# Printrhub_Rev_1.net
KiCad netlist of a schematic drawn in EAGLE
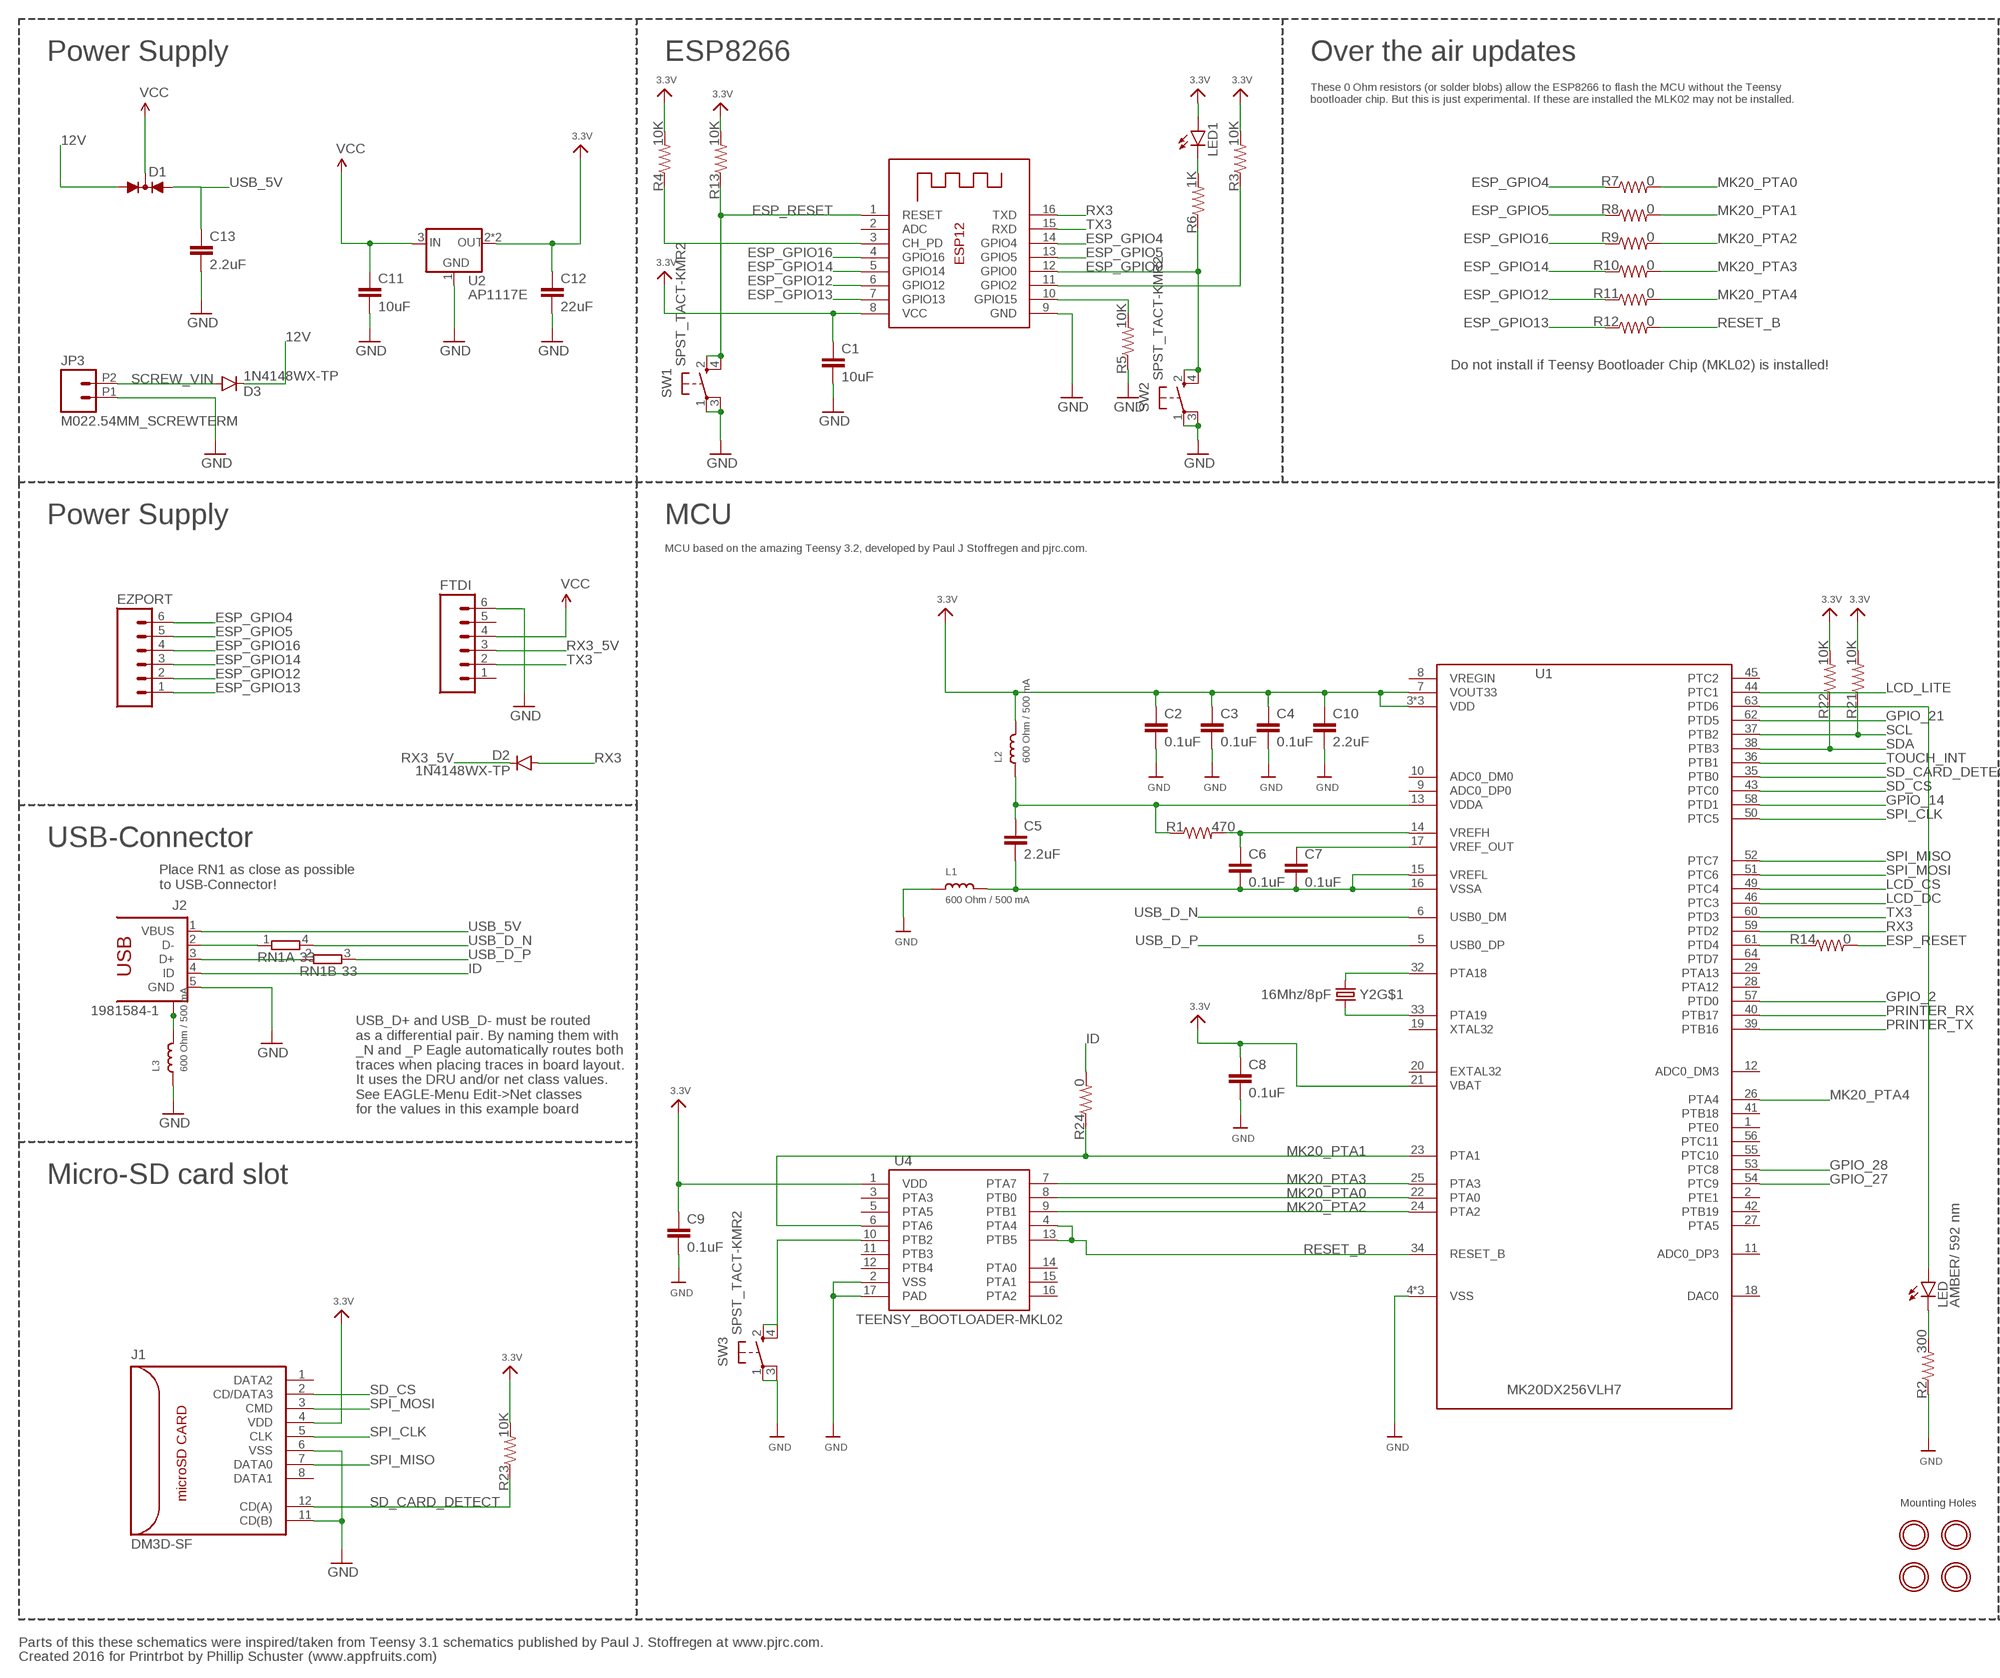
[diagram p0: schematic, sheet 1, part 1 of 2]
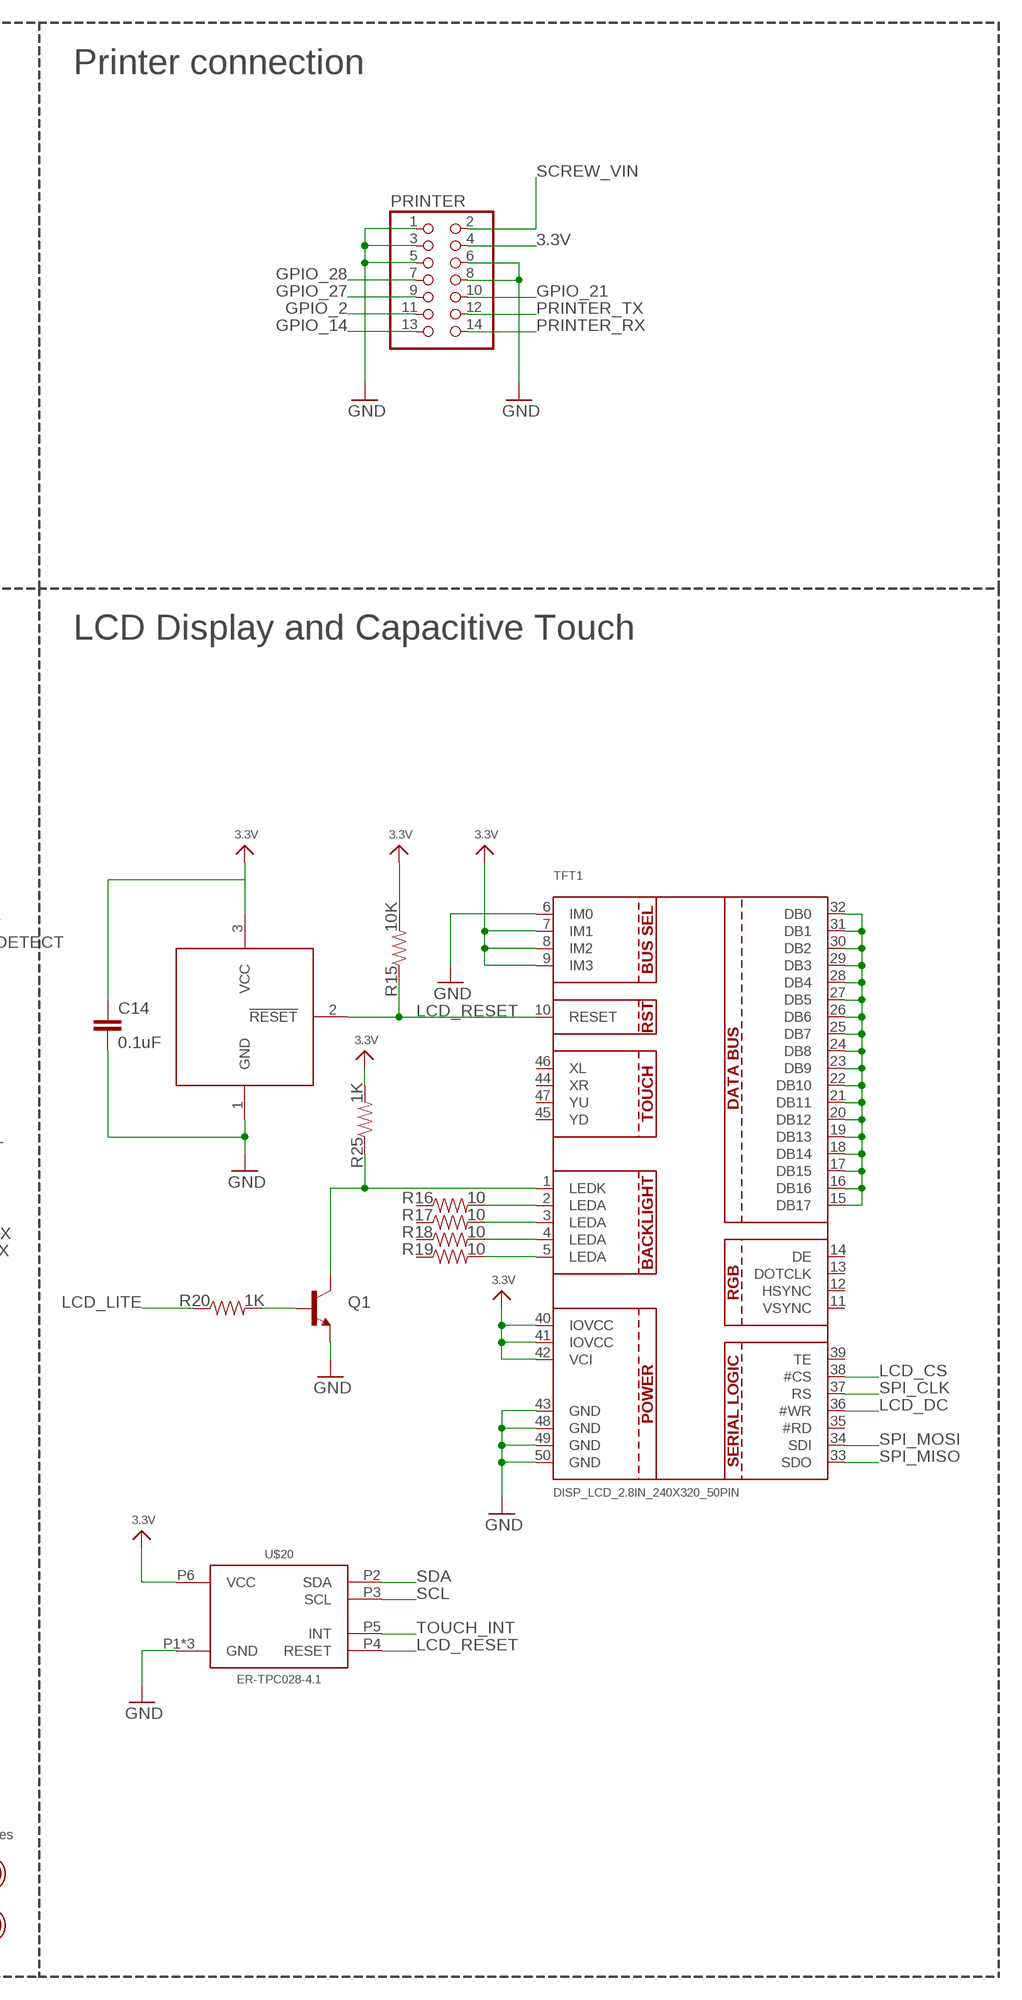
[diagram p1: schematic, sheet 1, part 2 of 2]

(export (version "E")
  (design (tool "Eeschema 10.0.6"))
  (components
    (comp (ref "C1")
      (value "10uF")
      (footprint "eagle-import:0603-CAP")
      (fields (field (name "MF") "Murata") (field (name "MPN") "GRM188R60J106ME47D"))
      (libsource (lib "eagle-import") (part "CAPACITOR-10UF"))
    )
    (comp (ref "C2")
      (value "0.1uF")
      (footprint "eagle-import:0603-CAP")
      (fields (field (name "MF") "Kemet") (field (name "MPN") "C0603C104J3RACTU"))
      (libsource (lib "eagle-import") (part "CAPACITOR-0.1UF"))
    )
    (comp (ref "C3")
      (value "0.1uF")
      (footprint "eagle-import:0603-CAP")
      (fields (field (name "MF") "Kemet") (field (name "MPN") "C0603C104J3RACTU"))
      (libsource (lib "eagle-import") (part "CAPACITOR-0.1UF"))
    )
    (comp (ref "C4")
      (value "0.1uF")
      (footprint "eagle-import:0603-CAP")
      (fields (field (name "MF") "Kemet") (field (name "MPN") "C0603C104J3RACTU"))
      (libsource (lib "eagle-import") (part "CAPACITOR-0.1UF"))
    )
    (comp (ref "C5")
      (value "2.2uF")
      (footprint "eagle-import:0603-CAP")
      (fields (field (name "MF") "Kemet") (field (name "MPN") "C0603C225K4PACTU"))
      (libsource (lib "eagle-import") (part "CAPACITOR-2.2UF"))
    )
    (comp (ref "C6")
      (value "0.1uF")
      (footprint "eagle-import:0603-CAP")
      (fields (field (name "MF") "Kemet") (field (name "MPN") "C0603C104J3RACTU"))
      (libsource (lib "eagle-import") (part "CAPACITOR-0.1UF"))
    )
    (comp (ref "C7")
      (value "0.1uF")
      (footprint "eagle-import:0603-CAP")
      (fields (field (name "MF") "Kemet") (field (name "MPN") "C0603C104J3RACTU"))
      (libsource (lib "eagle-import") (part "CAPACITOR-0.1UF"))
    )
    (comp (ref "C8")
      (value "0.1uF")
      (footprint "eagle-import:0603-CAP")
      (fields (field (name "MF") "Kemet") (field (name "MPN") "C0603C104J3RACTU"))
      (libsource (lib "eagle-import") (part "CAPACITOR-0.1UF"))
    )
    (comp (ref "C9")
      (value "0.1uF")
      (footprint "eagle-import:0603-CAP")
      (fields (field (name "MF") "Kemet") (field (name "MPN") "C0603C104J3RACTU"))
      (libsource (lib "eagle-import") (part "CAPACITOR-0.1UF"))
    )
    (comp (ref "C10")
      (value "2.2uF")
      (footprint "eagle-import:0603-CAP")
      (fields (field (name "MF") "Kemet") (field (name "MPN") "C0603C225K4PACTU"))
      (libsource (lib "eagle-import") (part "CAPACITOR-2.2UF"))
    )
    (comp (ref "C11")
      (value "10uF")
      (footprint "eagle-import:0603-CAP")
      (fields (field (name "MF") "Murata") (field (name "MPN") "GRM188R60J106ME47D"))
      (libsource (lib "eagle-import") (part "CAPACITOR-10UF"))
    )
    (comp (ref "C12")
      (value "22uF")
      (footprint "eagle-import:0603-CAP")
      (fields (field (name "MF") "Murata") (field (name "MPN") "GRM188R60J226MEA0D"))
      (libsource (lib "eagle-import") (part "CAPACITOR-22UF"))
    )
    (comp (ref "C13")
      (value "2.2uF")
      (footprint "eagle-import:0603-CAP")
      (fields (field (name "MF") "Kemet") (field (name "MPN") "C0603C225K4PACTU"))
      (libsource (lib "eagle-import") (part "CAPACITOR-2.2UF"))
    )
    (comp (ref "C14")
      (value "0.1uF")
      (footprint "eagle-import:0603-CAP")
      (fields (field (name "MF") "Kemet") (field (name "MPN") "C0603C104J3RACTU"))
      (libsource (lib "eagle-import") (part "CAPACITOR-0.1UF"))
    )
    (comp (ref "D1")
      (value "DIODE-2AC|CASOT23")
      (footprint "eagle-import:SOT23")
      (libsource (lib "eagle-import") (part "DIODE-2AC|CASOT23"))
    )
    (comp (ref "D2")
      (value "1N4148WX-TP")
      (footprint "eagle-import:SOD-323")
      (fields (field (name "MF") "Micro Commercial Co"))
      (libsource (lib "eagle-import") (part "DIODESOD"))
    )
    (comp (ref "D3")
      (value "1N4148WX-TP")
      (footprint "eagle-import:SOD-323")
      (fields (field (name "MF") "Micro Commercial Co"))
      (libsource (lib "eagle-import") (part "DIODESOD"))
    )
    (comp (ref "EZPORT")
      (value "M06SMD-STRAIGHT")
      (footprint "eagle-import:1X06_SMD_STRAIGHT")
      (libsource (lib "eagle-import") (part "M06SMD-STRAIGHT"))
    )
    (comp (ref "FTDI")
      (value "M06SMD-STRAIGHT")
      (footprint "eagle-import:1X06_SMD_STRAIGHT")
      (libsource (lib "eagle-import") (part "M06SMD-STRAIGHT"))
    )
    (comp (ref "J1")
      (value "DM3D-SF")
      (footprint "eagle-import:DM3D-SF")
      (libsource (lib "eagle-import") (part "DM3D-SF"))
    )
    (comp (ref "J2")
      (value "1981584-1")
      (footprint "eagle-import:1981584-1")
      (libsource (lib "eagle-import") (part "1981584-1"))
    )
    (comp (ref "JP3")
      (value "M022.54MM_SCREWTERM")
      (footprint "eagle-import:1X02_2.54_SCREWTERM")
      (libsource (lib "eagle-import") (part "M022.54MM_SCREWTERM"))
    )
    (comp (ref "L1")
      (value "600 Ohm / 500 mA")
      (footprint "eagle-import:0603")
      (fields (field (name "MF") "Murata") (field (name "MPN") "BLM18AG601SN1D"))
      (libsource (lib "eagle-import") (part "INDUCTOR-0603_600OHM/500MA"))
    )
    (comp (ref "L2")
      (value "600 Ohm / 500 mA")
      (footprint "eagle-import:0603")
      (fields (field (name "MF") "Murata") (field (name "MPN") "BLM18AG601SN1D"))
      (libsource (lib "eagle-import") (part "INDUCTOR-0603_600OHM/500MA"))
    )
    (comp (ref "L3")
      (value "600 Ohm / 500 mA")
      (footprint "eagle-import:0603")
      (fields (field (name "MF") "Murata") (field (name "MPN") "BLM18AG601SN1D"))
      (libsource (lib "eagle-import") (part "INDUCTOR-0603_600OHM/500MA"))
    )
    (comp (ref "LED")
      (value "AMBER/ 592 nm")
      (footprint "eagle-import:LED-0603")
      (fields (field (name "MF") "Avago Technologies") (field (name "MPN") "HSMA-C190"))
      (libsource (lib "eagle-import") (part "LED-AMBER"))
    )
    (comp (ref "LED1")
      (value "LED-GREEN")
      (footprint "eagle-import:LED-0603")
      (fields (field (name "MF") "Avago") (field (name "MPN") "HSMG-C190"))
      (libsource (lib "eagle-import") (part "LED-GREEN"))
    )
    (comp (ref "PRINTER")
      (value "PINHD-2X7SMT")
      (footprint "eagle-import:2X07_SMT")
      (libsource (lib "eagle-import") (part "PINHD-2X7SMT"))
    )
    (comp (ref "Q1")
      (value "TRANSISTOR_NPNSOT23-3")
      (footprint "eagle-import:SOT23-3")
      (fields (field (name "MF") "ON Semiconductor") (field (name "MPN") "MMBT2222ALT1G"))
      (libsource (lib "eagle-import") (part "TRANSISTOR_NPNSOT23-3"))
    )
    (comp (ref "R1")
      (value "470")
      (footprint "eagle-import:0603-RES")
      (fields (field (name "MF") "Panasonic") (field (name "MPN") "ERJ-3GEYJ471V"))
      (libsource (lib "eagle-import") (part "RESISTOR-470"))
    )
    (comp (ref "R2")
      (value "300")
      (footprint "eagle-import:0603-RES")
      (libsource (lib "eagle-import") (part "RESISTOR0603"))
    )
    (comp (ref "R3")
      (value "10K")
      (footprint "eagle-import:0603-RES")
      (fields (field (name "MF") "Panasonic") (field (name "MPN") "ERJ-3GEYJ103V"))
      (libsource (lib "eagle-import") (part "RESISTOR-10K"))
    )
    (comp (ref "R4")
      (value "10K")
      (footprint "eagle-import:0603-RES")
      (fields (field (name "MF") "Panasonic") (field (name "MPN") "ERJ-3GEYJ103V"))
      (libsource (lib "eagle-import") (part "RESISTOR-10K"))
    )
    (comp (ref "R5")
      (value "10K")
      (footprint "eagle-import:0603-RES")
      (fields (field (name "MF") "Panasonic") (field (name "MPN") "ERJ-3GEYJ103V"))
      (libsource (lib "eagle-import") (part "RESISTOR-10K"))
    )
    (comp (ref "R6")
      (value "1K")
      (footprint "eagle-import:0603-RES")
      (fields (field (name "MF") "Panasonic") (field (name "MPN") "ERJ-3GEYJ102V"))
      (libsource (lib "eagle-import") (part "RESISTOR-1K"))
    )
    (comp (ref "R7")
      (value "0")
      (footprint "eagle-import:0603-RES")
      (fields (field (name "MF") "Panasonic") (field (name "MPN") "ERJ-3GEY0R00V"))
      (libsource (lib "eagle-import") (part "RESISTOR-0"))
    )
    (comp (ref "R8")
      (value "0")
      (footprint "eagle-import:0603-RES")
      (fields (field (name "MF") "Panasonic") (field (name "MPN") "ERJ-3GEY0R00V"))
      (libsource (lib "eagle-import") (part "RESISTOR-0"))
    )
    (comp (ref "R9")
      (value "0")
      (footprint "eagle-import:0603-RES")
      (fields (field (name "MF") "Panasonic") (field (name "MPN") "ERJ-3GEY0R00V"))
      (libsource (lib "eagle-import") (part "RESISTOR-0"))
    )
    (comp (ref "R10")
      (value "0")
      (footprint "eagle-import:0603-RES")
      (fields (field (name "MF") "Panasonic") (field (name "MPN") "ERJ-3GEY0R00V"))
      (libsource (lib "eagle-import") (part "RESISTOR-0"))
    )
    (comp (ref "R11")
      (value "0")
      (footprint "eagle-import:0603-RES")
      (fields (field (name "MF") "Panasonic") (field (name "MPN") "ERJ-3GEY0R00V"))
      (libsource (lib "eagle-import") (part "RESISTOR-0"))
    )
    (comp (ref "R12")
      (value "0")
      (footprint "eagle-import:0603-RES")
      (fields (field (name "MF") "Panasonic") (field (name "MPN") "ERJ-3GEY0R00V"))
      (libsource (lib "eagle-import") (part "RESISTOR-0"))
    )
    (comp (ref "R13")
      (value "10K")
      (footprint "eagle-import:0603-RES")
      (fields (field (name "MF") "Panasonic") (field (name "MPN") "ERJ-3GEYJ103V"))
      (libsource (lib "eagle-import") (part "RESISTOR-10K"))
    )
    (comp (ref "R14")
      (value "0")
      (footprint "eagle-import:0603-RES")
      (fields (field (name "MF") "Panasonic") (field (name "MPN") "ERJ-3GEY0R00V"))
      (libsource (lib "eagle-import") (part "RESISTOR-0"))
    )
    (comp (ref "R15")
      (value "10K")
      (footprint "eagle-import:0603-RES")
      (fields (field (name "MF") "Panasonic") (field (name "MPN") "ERJ-3GEYJ103V"))
      (libsource (lib "eagle-import") (part "RESISTOR-10K"))
    )
    (comp (ref "R16")
      (value "10")
      (footprint "eagle-import:0603-RES")
      (fields (field (name "MF") "Panasonic") (field (name "MPN") "ERJ-3EKF10R0V"))
      (libsource (lib "eagle-import") (part "RESISTOR-10"))
    )
    (comp (ref "R17")
      (value "10")
      (footprint "eagle-import:0603-RES")
      (fields (field (name "MF") "Panasonic") (field (name "MPN") "ERJ-3EKF10R0V"))
      (libsource (lib "eagle-import") (part "RESISTOR-10"))
    )
    (comp (ref "R18")
      (value "10")
      (footprint "eagle-import:0603-RES")
      (fields (field (name "MF") "Panasonic") (field (name "MPN") "ERJ-3EKF10R0V"))
      (libsource (lib "eagle-import") (part "RESISTOR-10"))
    )
    (comp (ref "R19")
      (value "10")
      (footprint "eagle-import:0603-RES")
      (fields (field (name "MF") "Panasonic") (field (name "MPN") "ERJ-3EKF10R0V"))
      (libsource (lib "eagle-import") (part "RESISTOR-10"))
    )
    (comp (ref "R20")
      (value "1K")
      (footprint "eagle-import:0603-RES")
      (fields (field (name "MF") "Panasonic") (field (name "MPN") "ERJ-3GEYJ102V"))
      (libsource (lib "eagle-import") (part "RESISTOR-1K"))
    )
    (comp (ref "R21")
      (value "10K")
      (footprint "eagle-import:0603-RES")
      (fields (field (name "MF") "Panasonic") (field (name "MPN") "ERJ-3GEYJ103V"))
      (libsource (lib "eagle-import") (part "RESISTOR-10K"))
    )
    (comp (ref "R22")
      (value "10K")
      (footprint "eagle-import:0603-RES")
      (fields (field (name "MF") "Panasonic") (field (name "MPN") "ERJ-3GEYJ103V"))
      (libsource (lib "eagle-import") (part "RESISTOR-10K"))
    )
    (comp (ref "R23")
      (value "10K")
      (footprint "eagle-import:0603-RES")
      (fields (field (name "MF") "Panasonic") (field (name "MPN") "ERJ-3GEYJ103V"))
      (libsource (lib "eagle-import") (part "RESISTOR-10K"))
    )
    (comp (ref "R24")
      (value "0")
      (footprint "eagle-import:0603-RES")
      (fields (field (name "MF") "Panasonic") (field (name "MPN") "ERJ-3GEY0R00V"))
      (libsource (lib "eagle-import") (part "RESISTOR-0"))
    )
    (comp (ref "R25")
      (value "1K")
      (footprint "eagle-import:0603-RES")
      (fields (field (name "MF") "Panasonic") (field (name "MPN") "ERJ-3GEYJ102V"))
      (libsource (lib "eagle-import") (part "RESISTOR-1K"))
    )
    (comp (ref "RN1")
      (value "33")
      (footprint "eagle-import:EXB34V")
      (fields (field (name "MF") "Panasonic") (field (name "MPN") "EXB-34V330JV"))
      (libsource (lib "eagle-import") (part "2R-NEXB34V"))
    )
    (comp (ref "SW1")
      (value "SPST_TACT-KMR2")
      (footprint "eagle-import:KMR2")
      (libsource (lib "eagle-import") (part "SPST_TACT-KMR2"))
    )
    (comp (ref "SW2")
      (value "SPST_TACT-KMR2")
      (footprint "eagle-import:KMR2")
      (libsource (lib "eagle-import") (part "SPST_TACT-KMR2"))
    )
    (comp (ref "SW3")
      (value "SPST_TACT-KMR2")
      (footprint "eagle-import:KMR2")
      (libsource (lib "eagle-import") (part "SPST_TACT-KMR2"))
    )
    (comp (ref "TFT1")
      (value "DISP_LCD_2.8IN_240X320_50PIN")
      (footprint "eagle-import:TFT_2.83IN_240X320_50PIN")
      (libsource (lib "eagle-import") (part "DISP_LCD_2.8IN_240X320_50PIN"))
    )
    (comp (ref "U$15")
      (value "MOUNTINGHOLE2.0")
      (footprint "eagle-import:MOUNTINGHOLE_2.0_PLATED")
      (libsource (lib "eagle-import") (part "MOUNTINGHOLE2.0"))
    )
    (comp (ref "U$16")
      (value "MOUNTINGHOLE2.0")
      (footprint "eagle-import:MOUNTINGHOLE_2.0_PLATED")
      (libsource (lib "eagle-import") (part "MOUNTINGHOLE2.0"))
    )
    (comp (ref "U$17")
      (value "MOUNTINGHOLE2.0")
      (footprint "eagle-import:MOUNTINGHOLE_2.0_PLATED")
      (libsource (lib "eagle-import") (part "MOUNTINGHOLE2.0"))
    )
    (comp (ref "U$18")
      (value "MOUNTINGHOLE2.0")
      (footprint "eagle-import:MOUNTINGHOLE_2.0_PLATED")
      (libsource (lib "eagle-import") (part "MOUNTINGHOLE2.0"))
    )
    (comp (ref "U$20")
      (value "ER-TPC028-4.1")
      (footprint "eagle-import:ER-CON06HB-1")
      (libsource (lib "eagle-import") (part "ER-TPC028-4.1"))
    )
    (comp (ref "U1")
      (value "MK20DX256VLH7")
      (footprint "eagle-import:MK20DX256VLH7")
      (fields (field (name "MF") "Freescale"))
      (libsource (lib "eagle-import") (part "MK20DX256VLH7"))
    )
    (comp (ref "U2")
      (value "AP1117E")
      (footprint "eagle-import:SOT223")
      (libsource (lib "eagle-import") (part "AP1117E"))
    )
    (comp (ref "U3")
      (value "MAX308-SOT23")
      (footprint "eagle-import:SOT23")
      (libsource (lib "eagle-import") (part "MAX308-SOT23"))
    )
    (comp (ref "U4")
      (value "TEENSY_BOOTLOADER-MKL02")
      (footprint "eagle-import:QFN50P300X300X100-17N")
      (libsource (lib "eagle-import") (part "TEENSY_BOOTLOADER-MKL02"))
    )
    (comp (ref "X1")
      (value "ESP-12")
      (footprint "eagle-import:ESP-12")
      (libsource (lib "eagle-import") (part "ESP-12"))
    )
    (comp (ref "Y2")
      (value "16Mhz/8pF")
      (footprint "eagle-import:CRYSTAL-SMD-5X3")
      (fields (field (name "MF") "ECS") (field (name "MPN") "ECS-160-8-30B-CKM"))
      (libsource (lib "eagle-import") (part "CRYSTAL/SMD-5X3-GND16MHZ/8PF"))
    )
  )
  (nets
    (net (code "1") (name "/12V") (class "Default")
      (node (ref "D1") (pin "1") (pinfunction "A1_1") (pintype "passive"))
      (node (ref "D3") (pin "C") (pinfunction "C_C") (pintype "passive"))
    )
    (net (code "2") (name "/ESP_GPIO0") (class "Default")
      (node (ref "R6") (pin "1") (pinfunction "1_1") (pintype "passive"))
      (node (ref "SW2") (pin "2") (pinfunction "S_2") (pintype "passive"))
      (node (ref "SW2") (pin "4") (pinfunction "S1_4") (pintype "passive"))
      (node (ref "X1") (pin "12") (pinfunction "GPIO0_12") (pintype "bidirectional"))
    )
    (net (code "3") (name "/ESP_GPIO4") (class "Default")
      (node (ref "EZPORT") (pin "6") (pinfunction "6_6") (pintype "passive"))
      (node (ref "R7") (pin "1") (pinfunction "1_1") (pintype "passive"))
      (node (ref "X1") (pin "14") (pinfunction "GPIO4_14") (pintype "bidirectional"))
    )
    (net (code "4") (name "/ESP_GPIO5") (class "Default")
      (node (ref "EZPORT") (pin "5") (pinfunction "5_5") (pintype "passive"))
      (node (ref "R8") (pin "1") (pinfunction "1_1") (pintype "passive"))
      (node (ref "X1") (pin "13") (pinfunction "GPIO5_13") (pintype "bidirectional"))
    )
    (net (code "5") (name "/ESP_GPIO12") (class "Default")
      (node (ref "EZPORT") (pin "2") (pinfunction "2_2") (pintype "passive"))
      (node (ref "R11") (pin "1") (pinfunction "1_1") (pintype "passive"))
      (node (ref "X1") (pin "6") (pinfunction "GPIO12_6") (pintype "bidirectional"))
    )
    (net (code "6") (name "/ESP_GPIO13") (class "Default")
      (node (ref "EZPORT") (pin "1") (pinfunction "1_1") (pintype "passive"))
      (node (ref "R12") (pin "1") (pinfunction "1_1") (pintype "passive"))
      (node (ref "X1") (pin "7") (pinfunction "GPIO13_7") (pintype "bidirectional"))
    )
    (net (code "7") (name "/ESP_GPIO14") (class "Default")
      (node (ref "EZPORT") (pin "3") (pinfunction "3_3") (pintype "passive"))
      (node (ref "R10") (pin "1") (pinfunction "1_1") (pintype "passive"))
      (node (ref "X1") (pin "5") (pinfunction "GPIO14_5") (pintype "bidirectional"))
    )
    (net (code "8") (name "/ESP_GPIO16") (class "Default")
      (node (ref "EZPORT") (pin "4") (pinfunction "4_4") (pintype "passive"))
      (node (ref "R9") (pin "1") (pinfunction "1_1") (pintype "passive"))
      (node (ref "X1") (pin "4") (pinfunction "GPIO16_4") (pintype "bidirectional"))
    )
    (net (code "9") (name "/ESP_RESET") (class "Default")
      (node (ref "R13") (pin "1") (pinfunction "1_1") (pintype "passive"))
      (node (ref "R14") (pin "2") (pinfunction "2_2") (pintype "passive"))
      (node (ref "SW1") (pin "2") (pinfunction "S_2") (pintype "passive"))
      (node (ref "SW1") (pin "4") (pinfunction "S1_4") (pintype "passive"))
      (node (ref "X1") (pin "1") (pinfunction "RESET_1") (pintype "input"))
    )
    (net (code "10") (name "/GPIO_2") (class "Default")
      (node (ref "PRINTER") (pin "11") (pinfunction "11_11") (pintype "passive"))
      (node (ref "U1") (pin "57") (pinfunction "PTD0_57") (pintype "bidirectional"))
    )
    (net (code "11") (name "/GPIO_14") (class "Default")
      (node (ref "PRINTER") (pin "13") (pinfunction "13_13") (pintype "passive"))
      (node (ref "U1") (pin "58") (pinfunction "PTD1_58") (pintype "bidirectional"))
    )
    (net (code "12") (name "/GPIO_21") (class "Default")
      (node (ref "PRINTER") (pin "10") (pinfunction "10_10") (pintype "passive"))
      (node (ref "U1") (pin "62") (pinfunction "PTD5_62") (pintype "bidirectional"))
    )
    (net (code "13") (name "/GPIO_27") (class "Default")
      (node (ref "PRINTER") (pin "9") (pinfunction "9_9") (pintype "passive"))
      (node (ref "U1") (pin "54") (pinfunction "PTC9_54") (pintype "bidirectional"))
    )
    (net (code "14") (name "/GPIO_28") (class "Default")
      (node (ref "PRINTER") (pin "7") (pinfunction "7_7") (pintype "passive"))
      (node (ref "U1") (pin "53") (pinfunction "PTC8_53") (pintype "bidirectional"))
    )
    (net (code "15") (name "/ID") (class "Default")
      (node (ref "J2") (pin "4") (pinfunction "ID_4") (pintype "passive"))
      (node (ref "R24") (pin "2") (pinfunction "2_2") (pintype "passive"))
    )
    (net (code "16") (name "/LCD_CS") (class "Default")
      (node (ref "TFT1") (pin "38") (pinfunction "#CS_38") (pintype "bidirectional"))
      (node (ref "U1") (pin "49") (pinfunction "PTC4_49") (pintype "bidirectional"))
    )
    (net (code "17") (name "/LCD_DC") (class "Default")
      (node (ref "TFT1") (pin "36") (pinfunction "#WR_36") (pintype "bidirectional"))
      (node (ref "U1") (pin "46") (pinfunction "PTC3_46") (pintype "bidirectional"))
    )
    (net (code "18") (name "/LCD_LITE") (class "Default")
      (node (ref "R20") (pin "1") (pinfunction "1_1") (pintype "passive"))
      (node (ref "U1") (pin "44") (pinfunction "PTC1_44") (pintype "bidirectional"))
    )
    (net (code "19") (name "/LCD_RESET") (class "Default")
      (node (ref "R15") (pin "1") (pinfunction "1_1") (pintype "passive"))
      (node (ref "TFT1") (pin "10") (pinfunction "RESET_10") (pintype "bidirectional"))
      (node (ref "U$20") (pin "P4") (pinfunction "RESET_P4") (pintype "bidirectional"))
      (node (ref "U3") (pin "2") (pinfunction "~{RESET}_2") (pintype "bidirectional"))
    )
    (net (code "20") (name "/MK20_PTA0") (class "Default")
      (node (ref "R7") (pin "2") (pinfunction "2_2") (pintype "passive"))
      (node (ref "U1") (pin "22") (pinfunction "PTA0_22") (pintype "bidirectional"))
      (node (ref "U4") (pin "8") (pinfunction "PTB0_8") (pintype "bidirectional"))
    )
    (net (code "21") (name "/MK20_PTA1") (class "Default")
      (node (ref "R24") (pin "1") (pinfunction "1_1") (pintype "passive"))
      (node (ref "R8") (pin "2") (pinfunction "2_2") (pintype "passive"))
      (node (ref "U1") (pin "23") (pinfunction "PTA1_23") (pintype "bidirectional"))
      (node (ref "U4") (pin "6") (pinfunction "PTA6_6") (pintype "bidirectional"))
    )
    (net (code "22") (name "/MK20_PTA2") (class "Default")
      (node (ref "R9") (pin "2") (pinfunction "2_2") (pintype "passive"))
      (node (ref "U1") (pin "24") (pinfunction "PTA2_24") (pintype "bidirectional"))
      (node (ref "U4") (pin "9") (pinfunction "PTB1_9") (pintype "bidirectional"))
    )
    (net (code "23") (name "/MK20_PTA3") (class "Default")
      (node (ref "R10") (pin "2") (pinfunction "2_2") (pintype "passive"))
      (node (ref "U1") (pin "25") (pinfunction "PTA3_25") (pintype "bidirectional"))
      (node (ref "U4") (pin "7") (pinfunction "PTA7_7") (pintype "bidirectional"))
    )
    (net (code "24") (name "/MK20_PTA4") (class "Default")
      (node (ref "R11") (pin "2") (pinfunction "2_2") (pintype "passive"))
      (node (ref "U1") (pin "26") (pinfunction "PTA4_26") (pintype "bidirectional"))
    )
    (net (code "25") (name "/PRINTER_RX") (class "Default")
      (node (ref "PRINTER") (pin "14") (pinfunction "14_14") (pintype "passive"))
      (node (ref "U1") (pin "40") (pinfunction "PTB17_40") (pintype "bidirectional"))
    )
    (net (code "26") (name "/PRINTER_TX") (class "Default")
      (node (ref "PRINTER") (pin "12") (pinfunction "12_12") (pintype "passive"))
      (node (ref "U1") (pin "39") (pinfunction "PTB16_39") (pintype "bidirectional"))
    )
    (net (code "27") (name "/RESET_B") (class "Default")
      (node (ref "R12") (pin "2") (pinfunction "2_2") (pintype "passive"))
      (node (ref "U1") (pin "34") (pinfunction "RESET_B_34") (pintype "bidirectional"))
      (node (ref "U4") (pin "13") (pinfunction "PTB5_13") (pintype "bidirectional"))
      (node (ref "U4") (pin "4") (pinfunction "PTA4_4") (pintype "bidirectional"))
    )
    (net (code "28") (name "/RX3") (class "Default")
      (node (ref "D2") (pin "A") (pinfunction "A_A") (pintype "passive"))
      (node (ref "U1") (pin "59") (pinfunction "PTD2_59") (pintype "bidirectional"))
      (node (ref "X1") (pin "16") (pinfunction "TXD_16") (pintype "output"))
    )
    (net (code "29") (name "/RX3_5V") (class "Default")
      (node (ref "D2") (pin "C") (pinfunction "C_C") (pintype "passive"))
      (node (ref "FTDI") (pin "3") (pinfunction "3_3") (pintype "passive"))
    )
    (net (code "30") (name "/SCL") (class "Default")
      (node (ref "R21") (pin "1") (pinfunction "1_1") (pintype "passive"))
      (node (ref "U$20") (pin "P3") (pinfunction "SCL_P3") (pintype "bidirectional"))
      (node (ref "U1") (pin "37") (pinfunction "PTB2_37") (pintype "bidirectional"))
    )
    (net (code "31") (name "/SCREW_VIN") (class "Default")
      (node (ref "D3") (pin "A") (pinfunction "A_A") (pintype "passive"))
      (node (ref "JP3") (pin "P2") (pinfunction "2_P2") (pintype "passive"))
      (node (ref "PRINTER") (pin "2") (pinfunction "2_2") (pintype "passive"))
    )
    (net (code "32") (name "/SDA") (class "Default")
      (node (ref "R22") (pin "1") (pinfunction "1_1") (pintype "passive"))
      (node (ref "U$20") (pin "P2") (pinfunction "SDA_P2") (pintype "bidirectional"))
      (node (ref "U1") (pin "38") (pinfunction "PTB3_38") (pintype "bidirectional"))
    )
    (net (code "33") (name "/SD_CARD_DETECT") (class "Default")
      (node (ref "J1") (pin "12") (pinfunction "CD(A)_12") (pintype "bidirectional"))
      (node (ref "R23") (pin "1") (pinfunction "1_1") (pintype "passive"))
      (node (ref "U1") (pin "35") (pinfunction "PTB0_35") (pintype "bidirectional"))
    )
    (net (code "34") (name "/SD_CS") (class "Default")
      (node (ref "J1") (pin "2") (pinfunction "CD/DATA3_2") (pintype "bidirectional"))
      (node (ref "U1") (pin "43") (pinfunction "PTC0_43") (pintype "bidirectional"))
    )
    (net (code "35") (name "/SPI_CLK") (class "Default")
      (node (ref "J1") (pin "5") (pinfunction "CLK_5") (pintype "bidirectional"))
      (node (ref "TFT1") (pin "37") (pinfunction "RS_37") (pintype "bidirectional"))
      (node (ref "U1") (pin "50") (pinfunction "PTC5_50") (pintype "bidirectional"))
    )
    (net (code "36") (name "/SPI_MISO") (class "Default")
      (node (ref "J1") (pin "7") (pinfunction "DATA0_7") (pintype "bidirectional"))
      (node (ref "TFT1") (pin "33") (pinfunction "SDO_33") (pintype "bidirectional"))
      (node (ref "U1") (pin "52") (pinfunction "PTC7_52") (pintype "bidirectional"))
    )
    (net (code "37") (name "/SPI_MOSI") (class "Default")
      (node (ref "J1") (pin "3") (pinfunction "CMD_3") (pintype "bidirectional"))
      (node (ref "TFT1") (pin "34") (pinfunction "SDI_34") (pintype "bidirectional"))
      (node (ref "U1") (pin "51") (pinfunction "PTC6_51") (pintype "bidirectional"))
    )
    (net (code "38") (name "/TOUCH_INT") (class "Default")
      (node (ref "U$20") (pin "P5") (pinfunction "INT_P5") (pintype "bidirectional"))
      (node (ref "U1") (pin "36") (pinfunction "PTB1_36") (pintype "bidirectional"))
    )
    (net (code "39") (name "/TX3") (class "Default")
      (node (ref "FTDI") (pin "2") (pinfunction "2_2") (pintype "passive"))
      (node (ref "U1") (pin "60") (pinfunction "PTD3_60") (pintype "bidirectional"))
      (node (ref "X1") (pin "15") (pinfunction "RXD_15") (pintype "input"))
    )
    (net (code "40") (name "/USB_5V") (class "Default")
      (node (ref "C13") (pin "1") (pinfunction "1_1") (pintype "passive"))
      (node (ref "D1") (pin "2") (pinfunction "A2_2") (pintype "passive"))
      (node (ref "J2") (pin "1") (pinfunction "VBUS_1") (pintype "passive"))
    )
    (net (code "41") (name "/USB_D_N") (class "Default")
      (node (ref "RN1") (pin "4") (pinfunction "2_4") (pintype "passive"))
      (node (ref "U1") (pin "6") (pinfunction "USB0_DM_6") (pintype "bidirectional"))
    )
    (net (code "42") (name "/USB_D_P") (class "Default")
      (node (ref "RN1") (pin "3") (pinfunction "2_3") (pintype "passive"))
      (node (ref "U1") (pin "5") (pinfunction "USB0_DP_5") (pintype "bidirectional"))
    )
    (net (code "43") (name "3.3V") (class "Default")
      (node (ref "C1") (pin "1") (pinfunction "1_1") (pintype "passive"))
      (node (ref "C10") (pin "1") (pinfunction "1_1") (pintype "passive"))
      (node (ref "C12") (pin "1") (pinfunction "1_1") (pintype "passive"))
      (node (ref "C14") (pin "1") (pinfunction "1_1") (pintype "passive"))
      (node (ref "C2") (pin "1") (pinfunction "1_1") (pintype "passive"))
      (node (ref "C3") (pin "1") (pinfunction "1_1") (pintype "passive"))
      (node (ref "C4") (pin "1") (pinfunction "1_1") (pintype "passive"))
      (node (ref "C8") (pin "1") (pinfunction "1_1") (pintype "passive"))
      (node (ref "C9") (pin "1") (pinfunction "1_1") (pintype "passive"))
      (node (ref "J1") (pin "4") (pinfunction "VDD_4") (pintype "power_in"))
      (node (ref "L2") (pin "2") (pinfunction "2_2") (pintype "passive"))
      (node (ref "LED1") (pin "A") (pinfunction "A_A") (pintype "passive"))
      (node (ref "PRINTER") (pin "4") (pinfunction "4_4") (pintype "passive"))
      (node (ref "R13") (pin "2") (pinfunction "2_2") (pintype "passive"))
      (node (ref "R15") (pin "2") (pinfunction "2_2") (pintype "passive"))
      (node (ref "R21") (pin "2") (pinfunction "2_2") (pintype "passive"))
      (node (ref "R22") (pin "2") (pinfunction "2_2") (pintype "passive"))
      (node (ref "R23") (pin "2") (pinfunction "2_2") (pintype "passive"))
      (node (ref "R25") (pin "2") (pinfunction "2_2") (pintype "passive"))
      (node (ref "R3") (pin "2") (pinfunction "2_2") (pintype "passive"))
      (node (ref "R4") (pin "2") (pinfunction "2_2") (pintype "passive"))
      (node (ref "TFT1") (pin "40") (pinfunction "IOVCC_40") (pintype "bidirectional"))
      (node (ref "TFT1") (pin "41") (pinfunction "IOVCC_41") (pintype "bidirectional"))
      (node (ref "TFT1") (pin "42") (pinfunction "VCI_42") (pintype "bidirectional"))
      (node (ref "TFT1") (pin "7") (pinfunction "IM1_7") (pintype "bidirectional"))
      (node (ref "TFT1") (pin "8") (pinfunction "IM2_8") (pintype "bidirectional"))
      (node (ref "TFT1") (pin "9") (pinfunction "IM3_9") (pintype "bidirectional"))
      (node (ref "U$20") (pin "P6") (pinfunction "VCC_P6") (pintype "bidirectional"))
      (node (ref "U1") (pin "21") (pinfunction "VBAT_21") (pintype "bidirectional"))
      (node (ref "U1") (pin "3") (pinfunction "VDD_3") (pintype "bidirectional"))
      (node (ref "U1") (pin "30") (pinfunction "VDD_30") (pintype "bidirectional"))
      (node (ref "U1") (pin "48") (pinfunction "VDD_48") (pintype "bidirectional"))
      (node (ref "U1") (pin "7") (pinfunction "VOUT33_7") (pintype "bidirectional"))
      (node (ref "U2") (pin "2") (pinfunction "OUT_2") (pintype "passive"))
      (node (ref "U2") (pin "4") (pinfunction "OUT_4") (pintype "passive"))
      (node (ref "U3") (pin "3") (pinfunction "VCC_3") (pintype "bidirectional"))
      (node (ref "U4") (pin "1") (pinfunction "VDD_1") (pintype "power_in"))
      (node (ref "X1") (pin "8") (pinfunction "VCC_8") (pintype "power_in"))
    )
    (net (code "44") (name "GND") (class "Default")
      (node (ref "C1") (pin "2") (pinfunction "2_2") (pintype "passive"))
      (node (ref "C10") (pin "2") (pinfunction "2_2") (pintype "passive"))
      (node (ref "C11") (pin "2") (pinfunction "2_2") (pintype "passive"))
      (node (ref "C12") (pin "2") (pinfunction "2_2") (pintype "passive"))
      (node (ref "C13") (pin "2") (pinfunction "2_2") (pintype "passive"))
      (node (ref "C14") (pin "2") (pinfunction "2_2") (pintype "passive"))
      (node (ref "C2") (pin "2") (pinfunction "2_2") (pintype "passive"))
      (node (ref "C3") (pin "2") (pinfunction "2_2") (pintype "passive"))
      (node (ref "C4") (pin "2") (pinfunction "2_2") (pintype "passive"))
      (node (ref "C8") (pin "2") (pinfunction "2_2") (pintype "passive"))
      (node (ref "C9") (pin "2") (pinfunction "2_2") (pintype "passive"))
      (node (ref "FTDI") (pin "6") (pinfunction "6_6") (pintype "passive"))
      (node (ref "J1") (pin "11") (pinfunction "CD(B)_11") (pintype "bidirectional"))
      (node (ref "J1") (pin "6") (pinfunction "VSS_6") (pintype "power_in"))
      (node (ref "J2") (pin "5") (pinfunction "GND_5") (pintype "passive"))
      (node (ref "JP3") (pin "P1") (pinfunction "1_P1") (pintype "passive"))
      (node (ref "L1") (pin "1") (pinfunction "1_1") (pintype "passive"))
      (node (ref "L3") (pin "1") (pinfunction "1_1") (pintype "passive"))
      (node (ref "PRINTER") (pin "1") (pinfunction "1_1") (pintype "passive"))
      (node (ref "PRINTER") (pin "3") (pinfunction "3_3") (pintype "passive"))
      (node (ref "PRINTER") (pin "5") (pinfunction "5_5") (pintype "passive"))
      (node (ref "PRINTER") (pin "6") (pinfunction "6_6") (pintype "passive"))
      (node (ref "PRINTER") (pin "8") (pinfunction "8_8") (pintype "passive"))
      (node (ref "Q1") (pin "2") (pinfunction "E_2") (pintype "passive"))
      (node (ref "R2") (pin "1") (pinfunction "1_1") (pintype "passive"))
      (node (ref "R5") (pin "1") (pinfunction "1_1") (pintype "passive"))
      (node (ref "SW1") (pin "1") (pinfunction "P_1") (pintype "passive"))
      (node (ref "SW1") (pin "3") (pinfunction "P1_3") (pintype "passive"))
      (node (ref "SW2") (pin "1") (pinfunction "P_1") (pintype "passive"))
      (node (ref "SW2") (pin "3") (pinfunction "P1_3") (pintype "passive"))
      (node (ref "SW3") (pin "1") (pinfunction "P_1") (pintype "passive"))
      (node (ref "SW3") (pin "3") (pinfunction "P1_3") (pintype "passive"))
      (node (ref "TFT1") (pin "43") (pinfunction "GND_43") (pintype "bidirectional"))
      (node (ref "TFT1") (pin "48") (pinfunction "GND_48") (pintype "bidirectional"))
      (node (ref "TFT1") (pin "49") (pinfunction "GND_49") (pintype "bidirectional"))
      (node (ref "TFT1") (pin "50") (pinfunction "GND_50") (pintype "bidirectional"))
      (node (ref "TFT1") (pin "6") (pinfunction "IM0_6") (pintype "bidirectional"))
      (node (ref "U$20") (pin "P1") (pinfunction "GND_P1") (pintype "bidirectional"))
      (node (ref "U$20") (pin "PAD@0") (pinfunction "GND_PAD@0") (pintype "bidirectional"))
      (node (ref "U$20") (pin "PAD@1") (pinfunction "GND_PAD@1") (pintype "bidirectional"))
      (node (ref "U1") (pin "31") (pinfunction "VSS_31") (pintype "bidirectional"))
      (node (ref "U1") (pin "4") (pinfunction "VSS_4") (pintype "bidirectional"))
      (node (ref "U1") (pin "47") (pinfunction "VSS_47") (pintype "bidirectional"))
      (node (ref "U2") (pin "1") (pinfunction "GND_1") (pintype "input"))
      (node (ref "U3") (pin "1") (pinfunction "GND_1") (pintype "bidirectional"))
      (node (ref "U4") (pin "17") (pinfunction "PAD_17") (pintype "bidirectional"))
      (node (ref "U4") (pin "2") (pinfunction "VSS_2") (pintype "bidirectional"))
      (node (ref "X1") (pin "9") (pinfunction "GND_9") (pintype "power_in"))
    )
    (net (code "45") (name "Net-(J2-D+)") (class "Default")
      (node (ref "J2") (pin "3") (pinfunction "D+_3") (pintype "passive"))
      (node (ref "RN1") (pin "2") (pinfunction "1_2") (pintype "passive"))
    )
    (net (code "46") (name "Net-(J2-D-)") (class "Default")
      (node (ref "J2") (pin "2") (pinfunction "D-_2") (pintype "passive"))
      (node (ref "RN1") (pin "1") (pinfunction "1_1") (pintype "passive"))
    )
    (net (code "47") (name "Net-(J2-PadS1)") (class "Default")
      (node (ref "J2") (pin "S1") (pinfunction "S1_S1") (pintype "passive"))
      (node (ref "J2") (pin "S2") (pinfunction "S2_S2") (pintype "passive"))
      (node (ref "J2") (pin "S3") (pinfunction "S3_S3") (pintype "passive"))
      (node (ref "J2") (pin "S4") (pinfunction "S4_S4") (pintype "passive"))
      (node (ref "L3") (pin "2") (pinfunction "2_2") (pintype "passive"))
    )
    (net (code "48") (name "Net-(LED-PadC)") (class "Default")
      (node (ref "LED") (pin "C") (pinfunction "C_C") (pintype "passive"))
      (node (ref "R2") (pin "2") (pinfunction "2_2") (pintype "passive"))
    )
    (net (code "49") (name "Net-(LED1-PadC)") (class "Default")
      (node (ref "LED1") (pin "C") (pinfunction "C_C") (pintype "passive"))
      (node (ref "R6") (pin "2") (pinfunction "2_2") (pintype "passive"))
    )
    (net (code "50") (name "Net-(Q1-B)") (class "Default")
      (node (ref "Q1") (pin "1") (pinfunction "B_1") (pintype "passive"))
      (node (ref "R20") (pin "2") (pinfunction "2_2") (pintype "passive"))
    )
    (net (code "51") (name "Net-(Q1-C)") (class "Default")
      (node (ref "Q1") (pin "3") (pinfunction "C_3") (pintype "passive"))
      (node (ref "R25") (pin "1") (pinfunction "1_1") (pintype "passive"))
      (node (ref "TFT1") (pin "1") (pinfunction "LEDK_1") (pintype "bidirectional"))
    )
    (net (code "52") (name "Net-(R16-Pad2)") (class "Default")
      (node (ref "R16") (pin "2") (pinfunction "2_2") (pintype "passive"))
      (node (ref "TFT1") (pin "2") (pinfunction "LEDA_2") (pintype "bidirectional"))
    )
    (net (code "53") (name "Net-(R17-Pad2)") (class "Default")
      (node (ref "R17") (pin "2") (pinfunction "2_2") (pintype "passive"))
      (node (ref "TFT1") (pin "3") (pinfunction "LEDA_3") (pintype "bidirectional"))
    )
    (net (code "54") (name "Net-(R18-Pad2)") (class "Default")
      (node (ref "R18") (pin "2") (pinfunction "2_2") (pintype "passive"))
      (node (ref "TFT1") (pin "4") (pinfunction "LEDA_4") (pintype "bidirectional"))
    )
    (net (code "55") (name "Net-(R19-Pad2)") (class "Default")
      (node (ref "R19") (pin "2") (pinfunction "2_2") (pintype "passive"))
      (node (ref "TFT1") (pin "5") (pinfunction "LEDA_5") (pintype "bidirectional"))
    )
    (net (code "56") (name "Net-(SW3-S)") (class "Default")
      (node (ref "SW3") (pin "2") (pinfunction "S_2") (pintype "passive"))
      (node (ref "SW3") (pin "4") (pinfunction "S1_4") (pintype "passive"))
      (node (ref "U4") (pin "10") (pinfunction "PTB2_10") (pintype "bidirectional"))
    )
    (net (code "57") (name "Net-(TFT1-DB0)") (class "Default")
      (node (ref "TFT1") (pin "15") (pinfunction "DB17_15") (pintype "bidirectional"))
      (node (ref "TFT1") (pin "16") (pinfunction "DB16_16") (pintype "bidirectional"))
      (node (ref "TFT1") (pin "17") (pinfunction "DB15_17") (pintype "bidirectional"))
      (node (ref "TFT1") (pin "18") (pinfunction "DB14_18") (pintype "bidirectional"))
      (node (ref "TFT1") (pin "19") (pinfunction "DB13_19") (pintype "bidirectional"))
      (node (ref "TFT1") (pin "20") (pinfunction "DB12_20") (pintype "bidirectional"))
      (node (ref "TFT1") (pin "21") (pinfunction "DB11_21") (pintype "bidirectional"))
      (node (ref "TFT1") (pin "22") (pinfunction "DB10_22") (pintype "bidirectional"))
      (node (ref "TFT1") (pin "23") (pinfunction "DB9_23") (pintype "bidirectional"))
      (node (ref "TFT1") (pin "24") (pinfunction "DB8_24") (pintype "bidirectional"))
      (node (ref "TFT1") (pin "25") (pinfunction "DB7_25") (pintype "bidirectional"))
      (node (ref "TFT1") (pin "26") (pinfunction "DB6_26") (pintype "bidirectional"))
      (node (ref "TFT1") (pin "27") (pinfunction "DB5_27") (pintype "bidirectional"))
      (node (ref "TFT1") (pin "28") (pinfunction "DB4_28") (pintype "bidirectional"))
      (node (ref "TFT1") (pin "29") (pinfunction "DB3_29") (pintype "bidirectional"))
      (node (ref "TFT1") (pin "30") (pinfunction "DB2_30") (pintype "bidirectional"))
      (node (ref "TFT1") (pin "31") (pinfunction "DB1_31") (pintype "bidirectional"))
      (node (ref "TFT1") (pin "32") (pinfunction "DB0_32") (pintype "bidirectional"))
    )
    (net (code "58") (name "Net-(U1-PTA18)") (class "Default")
      (node (ref "U1") (pin "32") (pinfunction "PTA18_32") (pintype "bidirectional"))
      (node (ref "Y2") (pin "3") (pinfunction "2_3") (pintype "passive"))
    )
    (net (code "59") (name "Net-(U1-PTA19)") (class "Default")
      (node (ref "U1") (pin "33") (pinfunction "PTA19_33") (pintype "bidirectional"))
      (node (ref "Y2") (pin "1") (pinfunction "1_1") (pintype "passive"))
    )
    (net (code "60") (name "Net-(U1-PTD4)") (class "Default")
      (node (ref "R14") (pin "1") (pinfunction "1_1") (pintype "passive"))
      (node (ref "U1") (pin "61") (pinfunction "PTD4_61") (pintype "bidirectional"))
    )
    (net (code "61") (name "Net-(U1-PTD6)") (class "Default")
      (node (ref "LED") (pin "A") (pinfunction "A_A") (pintype "passive"))
      (node (ref "U1") (pin "63") (pinfunction "PTD6_63") (pintype "bidirectional"))
    )
    (net (code "62") (name "Net-(U1-VDDA)") (class "Default")
      (node (ref "C5") (pin "1") (pinfunction "1_1") (pintype "passive"))
      (node (ref "L2") (pin "1") (pinfunction "1_1") (pintype "passive"))
      (node (ref "R1") (pin "1") (pinfunction "1_1") (pintype "passive"))
      (node (ref "U1") (pin "13") (pinfunction "VDDA_13") (pintype "bidirectional"))
    )
    (net (code "63") (name "Net-(U1-VREFH)") (class "Default")
      (node (ref "C6") (pin "1") (pinfunction "1_1") (pintype "passive"))
      (node (ref "R1") (pin "2") (pinfunction "2_2") (pintype "passive"))
      (node (ref "U1") (pin "14") (pinfunction "VREFH_14") (pintype "bidirectional"))
    )
    (net (code "64") (name "Net-(U1-VREFL)") (class "Default")
      (node (ref "C5") (pin "2") (pinfunction "2_2") (pintype "passive"))
      (node (ref "C6") (pin "2") (pinfunction "2_2") (pintype "passive"))
      (node (ref "C7") (pin "2") (pinfunction "2_2") (pintype "passive"))
      (node (ref "L1") (pin "2") (pinfunction "2_2") (pintype "passive"))
      (node (ref "U1") (pin "15") (pinfunction "VREFL_15") (pintype "bidirectional"))
      (node (ref "U1") (pin "16") (pinfunction "VSSA_16") (pintype "bidirectional"))
    )
    (net (code "65") (name "Net-(U1-VREF_OUT)") (class "Default")
      (node (ref "C7") (pin "1") (pinfunction "1_1") (pintype "passive"))
      (node (ref "U1") (pin "17") (pinfunction "VREF_OUT_17") (pintype "bidirectional"))
    )
    (net (code "66") (name "Net-(X1-CH_PD)") (class "Default")
      (node (ref "R4") (pin "1") (pinfunction "1_1") (pintype "passive"))
      (node (ref "X1") (pin "3") (pinfunction "CH_PD_3") (pintype "input"))
    )
    (net (code "67") (name "Net-(X1-GPIO2)") (class "Default")
      (node (ref "R3") (pin "1") (pinfunction "1_1") (pintype "passive"))
      (node (ref "X1") (pin "11") (pinfunction "GPIO2_11") (pintype "bidirectional"))
    )
    (net (code "68") (name "Net-(X1-GPIO15)") (class "Default")
      (node (ref "R5") (pin "2") (pinfunction "2_2") (pintype "passive"))
      (node (ref "X1") (pin "10") (pinfunction "GPIO15_10") (pintype "bidirectional"))
    )
    (net (code "69") (name "VCC") (class "Default")
      (node (ref "C11") (pin "1") (pinfunction "1_1") (pintype "passive"))
      (node (ref "D1") (pin "3") (pinfunction "C_3") (pintype "passive"))
      (node (ref "FTDI") (pin "4") (pinfunction "4_4") (pintype "passive"))
      (node (ref "U2") (pin "3") (pinfunction "IN_3") (pintype "input"))
    )
    (net (code "70") (name "unconnected-(FTDI-Pad1)") (class "Default")
      (node (ref "FTDI") (pin "1") (pinfunction "1_1") (pintype "passive"))
    )
    (net (code "71") (name "unconnected-(FTDI-Pad5)") (class "Default")
      (node (ref "FTDI") (pin "5") (pinfunction "5_5") (pintype "passive"))
    )
    (net (code "72") (name "unconnected-(J1B-DATA1-Pad8)") (class "Default")
      (node (ref "J1") (pin "8") (pinfunction "DATA1_8") (pintype "bidirectional"))
    )
    (net (code "73") (name "unconnected-(J1B-DATA2-Pad1)") (class "Default")
      (node (ref "J1") (pin "1") (pinfunction "DATA2_1") (pintype "bidirectional"))
    )
    (net (code "74") (name "unconnected-(R16-Pad1)") (class "Default")
      (node (ref "R16") (pin "1") (pinfunction "1_1") (pintype "passive"))
    )
    (net (code "75") (name "unconnected-(R17-Pad1)") (class "Default")
      (node (ref "R17") (pin "1") (pinfunction "1_1") (pintype "passive"))
    )
    (net (code "76") (name "unconnected-(R18-Pad1)") (class "Default")
      (node (ref "R18") (pin "1") (pinfunction "1_1") (pintype "passive"))
    )
    (net (code "77") (name "unconnected-(R19-Pad1)") (class "Default")
      (node (ref "R19") (pin "1") (pinfunction "1_1") (pintype "passive"))
    )
    (net (code "78") (name "unconnected-(TFT1-#RD-Pad35)") (class "Default")
      (node (ref "TFT1") (pin "35") (pinfunction "#RD_35") (pintype "bidirectional"))
    )
    (net (code "79") (name "unconnected-(TFT1-DE-Pad14)") (class "Default")
      (node (ref "TFT1") (pin "14") (pinfunction "DE_14") (pintype "bidirectional"))
    )
    (net (code "80") (name "unconnected-(TFT1-DOTCLK-Pad13)") (class "Default")
      (node (ref "TFT1") (pin "13") (pinfunction "DOTCLK_13") (pintype "bidirectional"))
    )
    (net (code "81") (name "unconnected-(TFT1-HSYNC-Pad12)") (class "Default")
      (node (ref "TFT1") (pin "12") (pinfunction "HSYNC_12") (pintype "bidirectional"))
    )
    (net (code "82") (name "unconnected-(TFT1-TE-Pad39)") (class "Default")
      (node (ref "TFT1") (pin "39") (pinfunction "TE_39") (pintype "bidirectional"))
    )
    (net (code "83") (name "unconnected-(TFT1-VSYNC-Pad11)") (class "Default")
      (node (ref "TFT1") (pin "11") (pinfunction "VSYNC_11") (pintype "bidirectional"))
    )
    (net (code "84") (name "unconnected-(TFT1-XL-Pad46)") (class "Default")
      (node (ref "TFT1") (pin "46") (pinfunction "XL_46") (pintype "bidirectional"))
    )
    (net (code "85") (name "unconnected-(TFT1-XR-Pad44)") (class "Default")
      (node (ref "TFT1") (pin "44") (pinfunction "XR_44") (pintype "bidirectional"))
    )
    (net (code "86") (name "unconnected-(TFT1-YD-Pad45)") (class "Default")
      (node (ref "TFT1") (pin "45") (pinfunction "YD_45") (pintype "bidirectional"))
    )
    (net (code "87") (name "unconnected-(TFT1-YU-Pad47)") (class "Default")
      (node (ref "TFT1") (pin "47") (pinfunction "YU_47") (pintype "bidirectional"))
    )
    (net (code "88") (name "unconnected-(U1-ADC0_DM0-Pad10)") (class "Default")
      (node (ref "U1") (pin "10") (pinfunction "ADC0_DM0_10") (pintype "bidirectional"))
    )
    (net (code "89") (name "unconnected-(U1-ADC0_DM3-Pad12)") (class "Default")
      (node (ref "U1") (pin "12") (pinfunction "ADC0_DM3_12") (pintype "bidirectional"))
    )
    (net (code "90") (name "unconnected-(U1-ADC0_DP0-Pad9)") (class "Default")
      (node (ref "U1") (pin "9") (pinfunction "ADC0_DP0_9") (pintype "bidirectional"))
    )
    (net (code "91") (name "unconnected-(U1-ADC0_DP3-Pad11)") (class "Default")
      (node (ref "U1") (pin "11") (pinfunction "ADC0_DP3_11") (pintype "bidirectional"))
    )
    (net (code "92") (name "unconnected-(U1-DAC0-Pad18)") (class "Default")
      (node (ref "U1") (pin "18") (pinfunction "DAC0_18") (pintype "bidirectional"))
    )
    (net (code "93") (name "unconnected-(U1-EXTAL32-Pad20)") (class "Default")
      (node (ref "U1") (pin "20") (pinfunction "EXTAL32_20") (pintype "bidirectional"))
    )
    (net (code "94") (name "unconnected-(U1-PTA5-Pad27)") (class "Default")
      (node (ref "U1") (pin "27") (pinfunction "PTA5_27") (pintype "bidirectional"))
    )
    (net (code "95") (name "unconnected-(U1-PTA12-Pad28)") (class "Default")
      (node (ref "U1") (pin "28") (pinfunction "PTA12_28") (pintype "bidirectional"))
    )
    (net (code "96") (name "unconnected-(U1-PTA13-Pad29)") (class "Default")
      (node (ref "U1") (pin "29") (pinfunction "PTA13_29") (pintype "bidirectional"))
    )
    (net (code "97") (name "unconnected-(U1-PTB18-Pad41)") (class "Default")
      (node (ref "U1") (pin "41") (pinfunction "PTB18_41") (pintype "bidirectional"))
    )
    (net (code "98") (name "unconnected-(U1-PTB19-Pad42)") (class "Default")
      (node (ref "U1") (pin "42") (pinfunction "PTB19_42") (pintype "bidirectional"))
    )
    (net (code "99") (name "unconnected-(U1-PTC2-Pad45)") (class "Default")
      (node (ref "U1") (pin "45") (pinfunction "PTC2_45") (pintype "bidirectional"))
    )
    (net (code "100") (name "unconnected-(U1-PTC10-Pad55)") (class "Default")
      (node (ref "U1") (pin "55") (pinfunction "PTC10_55") (pintype "bidirectional"))
    )
    (net (code "101") (name "unconnected-(U1-PTC11-Pad56)") (class "Default")
      (node (ref "U1") (pin "56") (pinfunction "PTC11_56") (pintype "bidirectional"))
    )
    (net (code "102") (name "unconnected-(U1-PTD7-Pad64)") (class "Default")
      (node (ref "U1") (pin "64") (pinfunction "PTD7_64") (pintype "bidirectional"))
    )
    (net (code "103") (name "unconnected-(U1-PTE0-Pad1)") (class "Default")
      (node (ref "U1") (pin "1") (pinfunction "PTE0_1") (pintype "bidirectional"))
    )
    (net (code "104") (name "unconnected-(U1-PTE1-Pad2)") (class "Default")
      (node (ref "U1") (pin "2") (pinfunction "PTE1_2") (pintype "bidirectional"))
    )
    (net (code "105") (name "unconnected-(U1-VREGIN-Pad8)") (class "Default")
      (node (ref "U1") (pin "8") (pinfunction "VREGIN_8") (pintype "bidirectional"))
    )
    (net (code "106") (name "unconnected-(U1-XTAL32-Pad19)") (class "Default")
      (node (ref "U1") (pin "19") (pinfunction "XTAL32_19") (pintype "bidirectional"))
    )
    (net (code "107") (name "unconnected-(U4-PTA0-Pad14)") (class "Default")
      (node (ref "U4") (pin "14") (pinfunction "PTA0_14") (pintype "bidirectional"))
    )
    (net (code "108") (name "unconnected-(U4-PTA1-Pad15)") (class "Default")
      (node (ref "U4") (pin "15") (pinfunction "PTA1_15") (pintype "bidirectional"))
    )
    (net (code "109") (name "unconnected-(U4-PTA2-Pad16)") (class "Default")
      (node (ref "U4") (pin "16") (pinfunction "PTA2_16") (pintype "bidirectional"))
    )
    (net (code "110") (name "unconnected-(U4-PTA3-Pad3)") (class "Default")
      (node (ref "U4") (pin "3") (pinfunction "PTA3_3") (pintype "bidirectional"))
    )
    (net (code "111") (name "unconnected-(U4-PTA5-Pad5)") (class "Default")
      (node (ref "U4") (pin "5") (pinfunction "PTA5_5") (pintype "bidirectional"))
    )
    (net (code "112") (name "unconnected-(U4-PTB3-Pad11)") (class "Default")
      (node (ref "U4") (pin "11") (pinfunction "PTB3_11") (pintype "bidirectional"))
    )
    (net (code "113") (name "unconnected-(U4-PTB4-Pad12)") (class "Default")
      (node (ref "U4") (pin "12") (pinfunction "PTB4_12") (pintype "bidirectional"))
    )
    (net (code "114") (name "unconnected-(X1-ADC-Pad2)") (class "Default")
      (node (ref "X1") (pin "2") (pinfunction "ADC_2") (pintype "passive"))
    )
  )
)
